# schema_v2_0.net
KiCad netlist of a schematic drawn in EAGLE
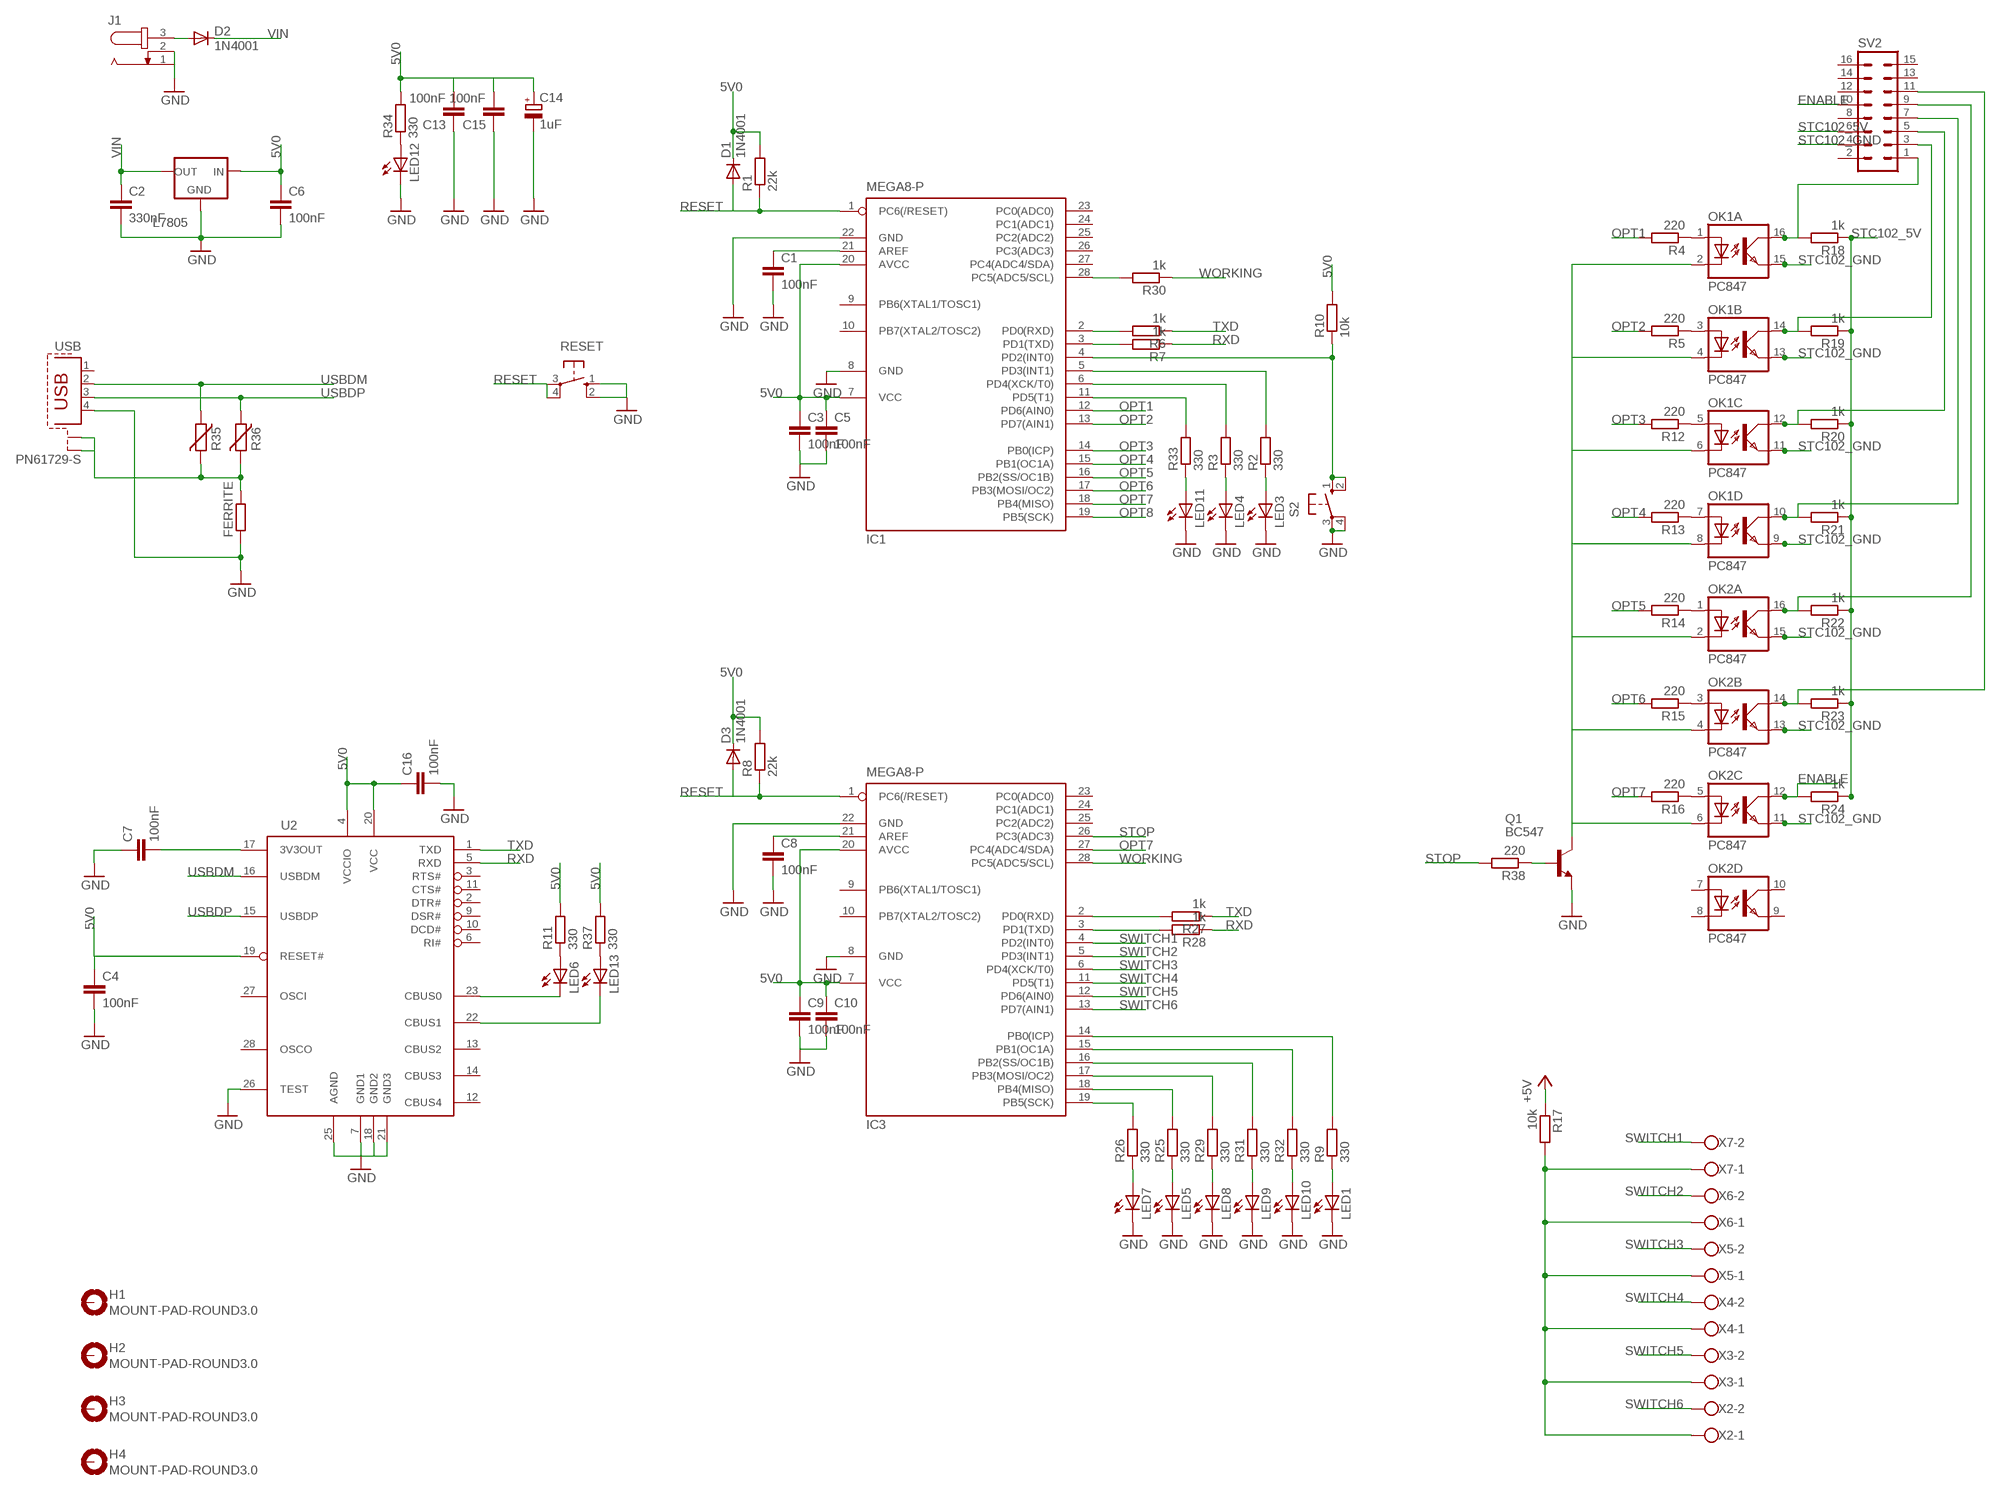
[diagram p0: schematic, sheet 1]

(export (version "E")
  (design (tool "Eeschema 10.0.6"))
  (components
    (comp (ref "C1")
      (value "100nF")
      (footprint "eagle-import:C025-025X050")
      (libsource (lib "eagle-import") (part "C-EU025-025X050"))
    )
    (comp (ref "C2")
      (value "330nF")
      (footprint "eagle-import:C025-025X050")
      (libsource (lib "eagle-import") (part "C-EU025-025X050"))
    )
    (comp (ref "C3")
      (value "100nF")
      (footprint "eagle-import:C025-025X050")
      (libsource (lib "eagle-import") (part "C-EU025-025X050"))
    )
    (comp (ref "C4")
      (value "100nF")
      (footprint "eagle-import:C0603K")
      (libsource (lib "eagle-import") (part "C-EUC0603K"))
    )
    (comp (ref "C5")
      (value "100nF")
      (footprint "eagle-import:C025-025X050")
      (libsource (lib "eagle-import") (part "C-EU025-025X050"))
    )
    (comp (ref "C6")
      (value "100nF")
      (footprint "eagle-import:C025-025X050")
      (libsource (lib "eagle-import") (part "C-EU025-025X050"))
    )
    (comp (ref "C7")
      (value "100nF")
      (footprint "eagle-import:C0603K")
      (libsource (lib "eagle-import") (part "C-EUC0603K"))
    )
    (comp (ref "C8")
      (value "100nF")
      (footprint "eagle-import:C025-025X050")
      (libsource (lib "eagle-import") (part "C-EU025-025X050"))
    )
    (comp (ref "C9")
      (value "100nF")
      (footprint "eagle-import:C025-025X050")
      (libsource (lib "eagle-import") (part "C-EU025-025X050"))
    )
    (comp (ref "C10")
      (value "100nF")
      (footprint "eagle-import:C025-025X050")
      (libsource (lib "eagle-import") (part "C-EU025-025X050"))
    )
    (comp (ref "C13")
      (value "100nF")
      (footprint "eagle-import:C025-025X050")
      (libsource (lib "eagle-import") (part "C-EU025-025X050"))
    )
    (comp (ref "C14")
      (value "1uF")
      (footprint "eagle-import:E2,5-5")
      (libsource (lib "eagle-import") (part "CPOL-EUE2.5-5"))
    )
    (comp (ref "C15")
      (value "100nF")
      (footprint "eagle-import:C025-025X050")
      (libsource (lib "eagle-import") (part "C-EU025-025X050"))
    )
    (comp (ref "C16")
      (value "100nF")
      (footprint "eagle-import:C0603K")
      (libsource (lib "eagle-import") (part "C-EUC0603K"))
    )
    (comp (ref "D1")
      (value "1N4001")
      (footprint "eagle-import:DO41-10")
      (libsource (lib "eagle-import") (part "1N4004"))
    )
    (comp (ref "D2")
      (value "1N4001")
      (footprint "eagle-import:DO41-10")
      (libsource (lib "eagle-import") (part "1N4004"))
    )
    (comp (ref "D3")
      (value "1N4001")
      (footprint "eagle-import:DO41-10")
      (libsource (lib "eagle-import") (part "1N4004"))
    )
    (comp (ref "FERRITE")
      (value "R-EU_M0805")
      (footprint "eagle-import:M0805")
      (libsource (lib "eagle-import") (part "resistor_R-EU_M0805"))
    )
    (comp (ref "H1")
      (value "MOUNT-PAD-ROUND3.0")
      (footprint "eagle-import:3,0-PAD")
      (libsource (lib "eagle-import") (part "MOUNT-PAD-ROUND3.0"))
    )
    (comp (ref "H2")
      (value "MOUNT-PAD-ROUND3.0")
      (footprint "eagle-import:3,0-PAD")
      (libsource (lib "eagle-import") (part "MOUNT-PAD-ROUND3.0"))
    )
    (comp (ref "H3")
      (value "MOUNT-PAD-ROUND3.0")
      (footprint "eagle-import:3,0-PAD")
      (libsource (lib "eagle-import") (part "MOUNT-PAD-ROUND3.0"))
    )
    (comp (ref "H4")
      (value "MOUNT-PAD-ROUND3.0")
      (footprint "eagle-import:3,0-PAD")
      (libsource (lib "eagle-import") (part "MOUNT-PAD-ROUND3.0"))
    )
    (comp (ref "IC1")
      (value "MEGA8-P")
      (footprint "eagle-import:DIL28-3")
      (libsource (lib "eagle-import") (part "MEGA8-P"))
    )
    (comp (ref "IC3")
      (value "MEGA8-P")
      (footprint "eagle-import:DIL28-3")
      (libsource (lib "eagle-import") (part "MEGA8-P"))
    )
    (comp (ref "J1")
      (value "JACK-PLUG0")
      (footprint "eagle-import:SPC4077")
      (libsource (lib "eagle-import") (part "JACK-PLUG0"))
    )
    (comp (ref "L7805")
      (value "79XXS")
      (footprint "eagle-import:79XXS")
      (libsource (lib "eagle-import") (part "79XXS"))
    )
    (comp (ref "LED1")
      (value "LED3MM")
      (footprint "eagle-import:LED3MM")
      (libsource (lib "eagle-import") (part "LED3MM"))
    )
    (comp (ref "LED3")
      (value "LED3MM")
      (footprint "eagle-import:LED3MM")
      (libsource (lib "eagle-import") (part "LED3MM"))
    )
    (comp (ref "LED4")
      (value "LED3MM")
      (footprint "eagle-import:LED3MM")
      (libsource (lib "eagle-import") (part "LED3MM"))
    )
    (comp (ref "LED5")
      (value "LED3MM")
      (footprint "eagle-import:LED3MM")
      (libsource (lib "eagle-import") (part "LED3MM"))
    )
    (comp (ref "LED6")
      (value "LED3MM")
      (footprint "eagle-import:LED3MM")
      (libsource (lib "eagle-import") (part "LED3MM"))
    )
    (comp (ref "LED7")
      (value "LED3MM")
      (footprint "eagle-import:LED3MM")
      (libsource (lib "eagle-import") (part "LED3MM"))
    )
    (comp (ref "LED8")
      (value "LED3MM")
      (footprint "eagle-import:LED3MM")
      (libsource (lib "eagle-import") (part "LED3MM"))
    )
    (comp (ref "LED9")
      (value "LED3MM")
      (footprint "eagle-import:LED3MM")
      (libsource (lib "eagle-import") (part "LED3MM"))
    )
    (comp (ref "LED10")
      (value "LED3MM")
      (footprint "eagle-import:LED3MM")
      (libsource (lib "eagle-import") (part "LED3MM"))
    )
    (comp (ref "LED11")
      (value "LED3MM")
      (footprint "eagle-import:LED3MM")
      (libsource (lib "eagle-import") (part "LED3MM"))
    )
    (comp (ref "LED12")
      (value "LED3MM")
      (footprint "eagle-import:LED3MM")
      (libsource (lib "eagle-import") (part "LED3MM"))
    )
    (comp (ref "LED13")
      (value "LED3MM")
      (footprint "eagle-import:LED3MM")
      (libsource (lib "eagle-import") (part "LED3MM"))
    )
    (comp (ref "OK1")
      (value "PC847")
      (footprint "eagle-import:DIL16")
      (libsource (lib "eagle-import") (part "PC847"))
    )
    (comp (ref "OK2")
      (value "PC847")
      (footprint "eagle-import:DIL16")
      (libsource (lib "eagle-import") (part "PC847"))
    )
    (comp (ref "Q1")
      (value "BC547")
      (footprint "eagle-import:TO92")
      (libsource (lib "eagle-import") (part "BC547"))
    )
    (comp (ref "R1")
      (value "22k")
      (footprint "eagle-import:0207_10")
      (libsource (lib "eagle-import") (part "R-EU_0207/10"))
    )
    (comp (ref "R2")
      (value "330")
      (footprint "eagle-import:0207_10")
      (libsource (lib "eagle-import") (part "R-EU_0207/10"))
    )
    (comp (ref "R3")
      (value "330")
      (footprint "eagle-import:0207_10")
      (libsource (lib "eagle-import") (part "R-EU_0207/10"))
    )
    (comp (ref "R4")
      (value "220")
      (footprint "eagle-import:0207_10")
      (libsource (lib "eagle-import") (part "R-EU_0207/10"))
    )
    (comp (ref "R5")
      (value "220")
      (footprint "eagle-import:0207_10")
      (libsource (lib "eagle-import") (part "R-EU_0207/10"))
    )
    (comp (ref "R6")
      (value "1k")
      (footprint "eagle-import:M1206")
      (libsource (lib "eagle-import") (part "R-EU_M1206"))
    )
    (comp (ref "R7")
      (value "1k")
      (footprint "eagle-import:M1206")
      (libsource (lib "eagle-import") (part "R-EU_M1206"))
    )
    (comp (ref "R8")
      (value "22k")
      (footprint "eagle-import:0207_10")
      (libsource (lib "eagle-import") (part "R-EU_0207/10"))
    )
    (comp (ref "R9")
      (value "330")
      (footprint "eagle-import:0207_10")
      (libsource (lib "eagle-import") (part "R-EU_0207/10"))
    )
    (comp (ref "R10")
      (value "10k")
      (footprint "eagle-import:0207_10")
      (libsource (lib "eagle-import") (part "R-EU_0207/10"))
    )
    (comp (ref "R11")
      (value "330")
      (footprint "eagle-import:0207_10")
      (libsource (lib "eagle-import") (part "R-EU_0207/10"))
    )
    (comp (ref "R12")
      (value "220")
      (footprint "eagle-import:0207_10")
      (libsource (lib "eagle-import") (part "R-EU_0207/10"))
    )
    (comp (ref "R13")
      (value "220")
      (footprint "eagle-import:0207_10")
      (libsource (lib "eagle-import") (part "R-EU_0207/10"))
    )
    (comp (ref "R14")
      (value "220")
      (footprint "eagle-import:0207_10")
      (libsource (lib "eagle-import") (part "R-EU_0207/10"))
    )
    (comp (ref "R15")
      (value "220")
      (footprint "eagle-import:0207_10")
      (libsource (lib "eagle-import") (part "R-EU_0207/10"))
    )
    (comp (ref "R16")
      (value "220")
      (footprint "eagle-import:0207_10")
      (libsource (lib "eagle-import") (part "R-EU_0207/10"))
    )
    (comp (ref "R17")
      (value "10k")
      (footprint "eagle-import:0207_10")
      (libsource (lib "eagle-import") (part "R-EU_0207/10"))
    )
    (comp (ref "R18")
      (value "1k")
      (footprint "eagle-import:0207_10")
      (libsource (lib "eagle-import") (part "R-EU_0207/10"))
    )
    (comp (ref "R19")
      (value "1k")
      (footprint "eagle-import:0207_10")
      (libsource (lib "eagle-import") (part "R-EU_0207/10"))
    )
    (comp (ref "R20")
      (value "1k")
      (footprint "eagle-import:0207_10")
      (libsource (lib "eagle-import") (part "R-EU_0207/10"))
    )
    (comp (ref "R21")
      (value "1k")
      (footprint "eagle-import:0207_10")
      (libsource (lib "eagle-import") (part "R-EU_0207/10"))
    )
    (comp (ref "R22")
      (value "1k")
      (footprint "eagle-import:0207_10")
      (libsource (lib "eagle-import") (part "R-EU_0207/10"))
    )
    (comp (ref "R23")
      (value "1k")
      (footprint "eagle-import:0207_10")
      (libsource (lib "eagle-import") (part "R-EU_0207/10"))
    )
    (comp (ref "R24")
      (value "1k")
      (footprint "eagle-import:0207_10")
      (libsource (lib "eagle-import") (part "R-EU_0207/10"))
    )
    (comp (ref "R25")
      (value "330")
      (footprint "eagle-import:0207_10")
      (libsource (lib "eagle-import") (part "R-EU_0207/10"))
    )
    (comp (ref "R26")
      (value "330")
      (footprint "eagle-import:0207_10")
      (libsource (lib "eagle-import") (part "R-EU_0207/10"))
    )
    (comp (ref "R27")
      (value "1k")
      (footprint "eagle-import:M1206")
      (libsource (lib "eagle-import") (part "R-EU_M1206"))
    )
    (comp (ref "R28")
      (value "1k")
      (footprint "eagle-import:M1206")
      (libsource (lib "eagle-import") (part "R-EU_M1206"))
    )
    (comp (ref "R29")
      (value "330")
      (footprint "eagle-import:0207_10")
      (libsource (lib "eagle-import") (part "R-EU_0207/10"))
    )
    (comp (ref "R30")
      (value "1k")
      (footprint "eagle-import:M1206")
      (libsource (lib "eagle-import") (part "R-EU_M1206"))
    )
    (comp (ref "R31")
      (value "330")
      (footprint "eagle-import:0207_10")
      (libsource (lib "eagle-import") (part "R-EU_0207/10"))
    )
    (comp (ref "R32")
      (value "330")
      (footprint "eagle-import:0207_10")
      (libsource (lib "eagle-import") (part "R-EU_0207/10"))
    )
    (comp (ref "R33")
      (value "330")
      (footprint "eagle-import:0207_10")
      (libsource (lib "eagle-import") (part "R-EU_0207/10"))
    )
    (comp (ref "R34")
      (value "330")
      (footprint "eagle-import:0207_10")
      (libsource (lib "eagle-import") (part "R-EU_0207/10"))
    )
    (comp (ref "R35")
      (value "VARISTORCN0603")
      (footprint "eagle-import:CT_CN0603")
      (libsource (lib "eagle-import") (part "VARISTORCN0603"))
    )
    (comp (ref "R36")
      (value "VARISTORCN0603")
      (footprint "eagle-import:CT_CN0603")
      (libsource (lib "eagle-import") (part "VARISTORCN0603"))
    )
    (comp (ref "R37")
      (value "330")
      (footprint "eagle-import:0207_10")
      (libsource (lib "eagle-import") (part "R-EU_0207/10"))
    )
    (comp (ref "R38")
      (value "220")
      (footprint "eagle-import:0207_10")
      (libsource (lib "eagle-import") (part "R-EU_0207/10"))
    )
    (comp (ref "RESET")
      (value "10-XX")
      (footprint "eagle-import:B3F-10XX")
      (fields (field (name "MPN") "B3F-1000"))
      (libsource (lib "eagle-import") (part "10-XX"))
    )
    (comp (ref "S2")
      (value "10-XX")
      (footprint "eagle-import:B3F-10XX")
      (fields (field (name "MPN") "B3F-1000"))
      (libsource (lib "eagle-import") (part "10-XX"))
    )
    (comp (ref "SV2")
      (value "MA08-2")
      (footprint "eagle-import:MA08-2")
      (libsource (lib "eagle-import") (part "MA08-2"))
    )
    (comp (ref "U2")
      (value "FT232RL")
      (footprint "eagle-import:SSOP28DB")
      (libsource (lib "eagle-import") (part "FT232RL"))
    )
    (comp (ref "USB")
      (value "PN61729-S")
      (footprint "eagle-import:PN61729-S")
      (fields (field (name "OC_FARNELL") "unknown") (field (name "OC_NEWARK") "unknown"))
      (libsource (lib "eagle-import") (part "PN61729-S"))
    )
    (comp (ref "X2")
      (value "W237-102")
      (footprint "eagle-import:W237-102")
      (fields (field (name "MPN") "237-102"))
      (libsource (lib "eagle-import") (part "W237-102"))
    )
    (comp (ref "X3")
      (value "W237-102")
      (footprint "eagle-import:W237-102")
      (fields (field (name "MPN") "237-102"))
      (libsource (lib "eagle-import") (part "W237-102"))
    )
    (comp (ref "X4")
      (value "W237-102")
      (footprint "eagle-import:W237-102")
      (fields (field (name "MPN") "237-102"))
      (libsource (lib "eagle-import") (part "W237-102"))
    )
    (comp (ref "X5")
      (value "W237-102")
      (footprint "eagle-import:W237-102")
      (fields (field (name "MPN") "237-102"))
      (libsource (lib "eagle-import") (part "W237-102"))
    )
    (comp (ref "X6")
      (value "W237-102")
      (footprint "eagle-import:W237-102")
      (fields (field (name "MPN") "237-102"))
      (libsource (lib "eagle-import") (part "W237-102"))
    )
    (comp (ref "X7")
      (value "W237-102")
      (footprint "eagle-import:W237-102")
      (fields (field (name "MPN") "237-102"))
      (libsource (lib "eagle-import") (part "W237-102"))
    )
  )
  (nets
    (net (code "1") (name "+5V") (class "Default")
      (node (ref "R17") (pin "1") (pinfunction "1_1") (pintype "passive"))
    )
    (net (code "2") (name "/5V0") (class "Default")
      (node (ref "C10") (pin "1") (pinfunction "1_1") (pintype "passive"))
      (node (ref "C13") (pin "2") (pinfunction "2_2") (pintype "passive"))
      (node (ref "C14") (pin "+") (pinfunction "+_+") (pintype "passive"))
      (node (ref "C15") (pin "2") (pinfunction "2_2") (pintype "passive"))
      (node (ref "C16") (pin "1") (pinfunction "1_1") (pintype "passive"))
      (node (ref "C3") (pin "1") (pinfunction "1_1") (pintype "passive"))
      (node (ref "C4") (pin "1") (pinfunction "1_1") (pintype "passive"))
      (node (ref "C5") (pin "1") (pinfunction "1_1") (pintype "passive"))
      (node (ref "C6") (pin "1") (pinfunction "1_1") (pintype "passive"))
      (node (ref "C9") (pin "1") (pinfunction "1_1") (pintype "passive"))
      (node (ref "D1") (pin "C") (pinfunction "C_C") (pintype "passive"))
      (node (ref "D3") (pin "C") (pinfunction "C_C") (pintype "passive"))
      (node (ref "IC1") (pin "20") (pinfunction "AVCC_20") (pintype "power_in"))
      (node (ref "IC1") (pin "7") (pinfunction "VCC_7") (pintype "power_in"))
      (node (ref "IC3") (pin "20") (pinfunction "AVCC_20") (pintype "power_in"))
      (node (ref "IC3") (pin "7") (pinfunction "VCC_7") (pintype "power_in"))
      (node (ref "L7805") (pin "IN") (pinfunction "IN_IN") (pintype "input"))
      (node (ref "R1") (pin "2") (pinfunction "2_2") (pintype "passive"))
      (node (ref "R10") (pin "2") (pinfunction "2_2") (pintype "passive"))
      (node (ref "R11") (pin "2") (pinfunction "2_2") (pintype "passive"))
      (node (ref "R34") (pin "2") (pinfunction "2_2") (pintype "passive"))
      (node (ref "R37") (pin "2") (pinfunction "2_2") (pintype "passive"))
      (node (ref "R8") (pin "2") (pinfunction "2_2") (pintype "passive"))
      (node (ref "U2") (pin "19") (pinfunction "RESET#_19") (pintype "input"))
      (node (ref "U2") (pin "20") (pinfunction "VCC_20") (pintype "power_in"))
      (node (ref "U2") (pin "4") (pinfunction "VCCIO_4") (pintype "power_in"))
    )
    (net (code "3") (name "/ENABLE") (class "Default")
      (node (ref "OK2") (pin "12") (pinfunction "COL_12") (pintype "passive"))
      (node (ref "R24") (pin "2") (pinfunction "2_2") (pintype "passive"))
      (node (ref "SV2") (pin "10") (pinfunction "10_10") (pintype "passive"))
    )
    (net (code "4") (name "/OPT1") (class "Default")
      (node (ref "IC1") (pin "12") (pinfunction "PD6(AIN0)_12") (pintype "bidirectional"))
      (node (ref "R4") (pin "2") (pinfunction "2_2") (pintype "passive"))
    )
    (net (code "5") (name "/OPT2") (class "Default")
      (node (ref "IC1") (pin "13") (pinfunction "PD7(AIN1)_13") (pintype "bidirectional"))
      (node (ref "R5") (pin "2") (pinfunction "2_2") (pintype "passive"))
    )
    (net (code "6") (name "/OPT3") (class "Default")
      (node (ref "IC1") (pin "14") (pinfunction "PB0(ICP)_14") (pintype "bidirectional"))
      (node (ref "R12") (pin "2") (pinfunction "2_2") (pintype "passive"))
    )
    (net (code "7") (name "/OPT4") (class "Default")
      (node (ref "IC1") (pin "15") (pinfunction "PB1(OC1A)_15") (pintype "bidirectional"))
      (node (ref "R13") (pin "2") (pinfunction "2_2") (pintype "passive"))
    )
    (net (code "8") (name "/OPT5") (class "Default")
      (node (ref "IC1") (pin "16") (pinfunction "PB2(SS/OC1B)_16") (pintype "bidirectional"))
      (node (ref "R14") (pin "2") (pinfunction "2_2") (pintype "passive"))
    )
    (net (code "9") (name "/OPT6") (class "Default")
      (node (ref "IC1") (pin "17") (pinfunction "PB3(MOSI/OC2)_17") (pintype "bidirectional"))
      (node (ref "R15") (pin "2") (pinfunction "2_2") (pintype "passive"))
    )
    (net (code "10") (name "/OPT7") (class "Default")
      (node (ref "IC1") (pin "18") (pinfunction "PB4(MISO)_18") (pintype "bidirectional"))
      (node (ref "IC3") (pin "27") (pinfunction "PC4(ADC4/SDA)_27") (pintype "bidirectional"))
      (node (ref "R16") (pin "2") (pinfunction "2_2") (pintype "passive"))
    )
    (net (code "11") (name "/OPT8") (class "Default")
      (node (ref "IC1") (pin "19") (pinfunction "PB5(SCK)_19") (pintype "bidirectional"))
    )
    (net (code "12") (name "/RESET") (class "Default")
      (node (ref "D1") (pin "A") (pinfunction "A_A") (pintype "passive"))
      (node (ref "D3") (pin "A") (pinfunction "A_A") (pintype "passive"))
      (node (ref "IC1") (pin "1") (pinfunction "PC6(/RESET)_1") (pintype "bidirectional"))
      (node (ref "IC3") (pin "1") (pinfunction "PC6(/RESET)_1") (pintype "bidirectional"))
      (node (ref "R1") (pin "1") (pinfunction "1_1") (pintype "passive"))
      (node (ref "R8") (pin "1") (pinfunction "1_1") (pintype "passive"))
      (node (ref "RESET") (pin "3") (pinfunction "P_3") (pintype "passive"))
      (node (ref "RESET") (pin "4") (pinfunction "P1_4") (pintype "passive"))
    )
    (net (code "13") (name "/RXD") (class "Default")
      (node (ref "R28") (pin "1") (pinfunction "1_1") (pintype "passive"))
      (node (ref "R7") (pin "1") (pinfunction "1_1") (pintype "passive"))
      (node (ref "U2") (pin "5") (pinfunction "RXD_5") (pintype "input"))
    )
    (net (code "14") (name "/STC102_5V") (class "Default")
      (node (ref "R18") (pin "1") (pinfunction "1_1") (pintype "passive"))
      (node (ref "R19") (pin "1") (pinfunction "1_1") (pintype "passive"))
      (node (ref "R20") (pin "1") (pinfunction "1_1") (pintype "passive"))
      (node (ref "R21") (pin "1") (pinfunction "1_1") (pintype "passive"))
      (node (ref "R22") (pin "1") (pinfunction "1_1") (pintype "passive"))
      (node (ref "R23") (pin "1") (pinfunction "1_1") (pintype "passive"))
      (node (ref "R24") (pin "1") (pinfunction "1_1") (pintype "passive"))
      (node (ref "SV2") (pin "6") (pinfunction "6_6") (pintype "passive"))
    )
    (net (code "15") (name "/STC102_GND") (class "Default")
      (node (ref "OK1") (pin "11") (pinfunction "EMIT_11") (pintype "passive"))
      (node (ref "OK1") (pin "13") (pinfunction "EMIT_13") (pintype "passive"))
      (node (ref "OK1") (pin "15") (pinfunction "EMIT_15") (pintype "passive"))
      (node (ref "OK1") (pin "9") (pinfunction "EMIT_9") (pintype "passive"))
      (node (ref "OK2") (pin "11") (pinfunction "EMIT_11") (pintype "passive"))
      (node (ref "OK2") (pin "13") (pinfunction "EMIT_13") (pintype "passive"))
      (node (ref "OK2") (pin "15") (pinfunction "EMIT_15") (pintype "passive"))
      (node (ref "SV2") (pin "4") (pinfunction "4_4") (pintype "passive"))
    )
    (net (code "16") (name "/STOP") (class "Default")
      (node (ref "IC3") (pin "26") (pinfunction "PC3(ADC3)_26") (pintype "bidirectional"))
      (node (ref "R38") (pin "2") (pinfunction "2_2") (pintype "passive"))
    )
    (net (code "17") (name "/SWITCH1") (class "Default")
      (node (ref "IC3") (pin "4") (pinfunction "PD2(INT0)_4") (pintype "bidirectional"))
      (node (ref "X7") (pin "2") (pinfunction "KL_2") (pintype "passive"))
    )
    (net (code "18") (name "/SWITCH2") (class "Default")
      (node (ref "IC3") (pin "5") (pinfunction "PD3(INT1)_5") (pintype "bidirectional"))
      (node (ref "X6") (pin "2") (pinfunction "KL_2") (pintype "passive"))
    )
    (net (code "19") (name "/SWITCH3") (class "Default")
      (node (ref "IC3") (pin "6") (pinfunction "PD4(XCK/T0)_6") (pintype "bidirectional"))
      (node (ref "X5") (pin "2") (pinfunction "KL_2") (pintype "passive"))
    )
    (net (code "20") (name "/SWITCH4") (class "Default")
      (node (ref "IC3") (pin "11") (pinfunction "PD5(T1)_11") (pintype "bidirectional"))
      (node (ref "X4") (pin "2") (pinfunction "KL_2") (pintype "passive"))
    )
    (net (code "21") (name "/SWITCH5") (class "Default")
      (node (ref "IC3") (pin "12") (pinfunction "PD6(AIN0)_12") (pintype "bidirectional"))
      (node (ref "X3") (pin "2") (pinfunction "KL_2") (pintype "passive"))
    )
    (net (code "22") (name "/SWITCH6") (class "Default")
      (node (ref "IC3") (pin "13") (pinfunction "PD7(AIN1)_13") (pintype "bidirectional"))
      (node (ref "X2") (pin "2") (pinfunction "KL_2") (pintype "passive"))
    )
    (net (code "23") (name "/TXD") (class "Default")
      (node (ref "R27") (pin "1") (pinfunction "1_1") (pintype "passive"))
      (node (ref "R6") (pin "1") (pinfunction "1_1") (pintype "passive"))
      (node (ref "U2") (pin "1") (pinfunction "TXD_1") (pintype "output"))
    )
    (net (code "24") (name "/USBDM") (class "Default")
      (node (ref "R35") (pin "1") (pinfunction "1_1") (pintype "passive"))
      (node (ref "U2") (pin "16") (pinfunction "USBDM_16") (pintype "bidirectional"))
      (node (ref "USB") (pin "2") (pinfunction "2_2") (pintype "passive"))
    )
    (net (code "25") (name "/USBDP") (class "Default")
      (node (ref "R36") (pin "1") (pinfunction "1_1") (pintype "passive"))
      (node (ref "U2") (pin "15") (pinfunction "USBDP_15") (pintype "bidirectional"))
      (node (ref "USB") (pin "3") (pinfunction "3_3") (pintype "passive"))
    )
    (net (code "26") (name "/VIN") (class "Default")
      (node (ref "C2") (pin "1") (pinfunction "1_1") (pintype "passive"))
      (node (ref "D2") (pin "C") (pinfunction "C_C") (pintype "passive"))
      (node (ref "L7805") (pin "OUT") (pinfunction "OUT_OUT") (pintype "passive"))
    )
    (net (code "27") (name "/WORKING") (class "Default")
      (node (ref "IC3") (pin "28") (pinfunction "PC5(ADC5/SCL)_28") (pintype "bidirectional"))
      (node (ref "R30") (pin "1") (pinfunction "1_1") (pintype "passive"))
    )
    (net (code "28") (name "GND") (class "Default")
      (node (ref "C1") (pin "2") (pinfunction "2_2") (pintype "passive"))
      (node (ref "C10") (pin "2") (pinfunction "2_2") (pintype "passive"))
      (node (ref "C13") (pin "1") (pinfunction "1_1") (pintype "passive"))
      (node (ref "C14") (pin "-") (pinfunction "-_-") (pintype "passive"))
      (node (ref "C15") (pin "1") (pinfunction "1_1") (pintype "passive"))
      (node (ref "C16") (pin "2") (pinfunction "2_2") (pintype "passive"))
      (node (ref "C2") (pin "2") (pinfunction "2_2") (pintype "passive"))
      (node (ref "C3") (pin "2") (pinfunction "2_2") (pintype "passive"))
      (node (ref "C4") (pin "2") (pinfunction "2_2") (pintype "passive"))
      (node (ref "C5") (pin "2") (pinfunction "2_2") (pintype "passive"))
      (node (ref "C6") (pin "2") (pinfunction "2_2") (pintype "passive"))
      (node (ref "C7") (pin "1") (pinfunction "1_1") (pintype "passive"))
      (node (ref "C8") (pin "2") (pinfunction "2_2") (pintype "passive"))
      (node (ref "C9") (pin "2") (pinfunction "2_2") (pintype "passive"))
      (node (ref "FERRITE") (pin "1") (pinfunction "1_1") (pintype "passive"))
      (node (ref "IC1") (pin "22") (pinfunction "GND_22") (pintype "power_in"))
      (node (ref "IC1") (pin "8") (pinfunction "GND_8") (pintype "power_in"))
      (node (ref "IC3") (pin "22") (pinfunction "GND_22") (pintype "power_in"))
      (node (ref "IC3") (pin "8") (pinfunction "GND_8") (pintype "power_in"))
      (node (ref "J1") (pin "1") (pinfunction "1_1") (pintype "passive"))
      (node (ref "J1") (pin "2") (pinfunction "2_2") (pintype "passive"))
      (node (ref "L7805") (pin "GND") (pinfunction "GND_GND") (pintype "input"))
      (node (ref "LED1") (pin "K") (pinfunction "C_K") (pintype "passive"))
      (node (ref "LED10") (pin "K") (pinfunction "C_K") (pintype "passive"))
      (node (ref "LED11") (pin "K") (pinfunction "C_K") (pintype "passive"))
      (node (ref "LED12") (pin "K") (pinfunction "C_K") (pintype "passive"))
      (node (ref "LED3") (pin "K") (pinfunction "C_K") (pintype "passive"))
      (node (ref "LED4") (pin "K") (pinfunction "C_K") (pintype "passive"))
      (node (ref "LED5") (pin "K") (pinfunction "C_K") (pintype "passive"))
      (node (ref "LED7") (pin "K") (pinfunction "C_K") (pintype "passive"))
      (node (ref "LED8") (pin "K") (pinfunction "C_K") (pintype "passive"))
      (node (ref "LED9") (pin "K") (pinfunction "C_K") (pintype "passive"))
      (node (ref "Q1") (pin "1") (pinfunction "E_1") (pintype "passive"))
      (node (ref "RESET") (pin "1") (pinfunction "S_1") (pintype "passive"))
      (node (ref "RESET") (pin "2") (pinfunction "S1_2") (pintype "passive"))
      (node (ref "S2") (pin "3") (pinfunction "P_3") (pintype "passive"))
      (node (ref "S2") (pin "4") (pinfunction "P1_4") (pintype "passive"))
      (node (ref "U2") (pin "18") (pinfunction "GND2_18") (pintype "power_in"))
      (node (ref "U2") (pin "21") (pinfunction "GND3_21") (pintype "power_in"))
      (node (ref "U2") (pin "25") (pinfunction "AGND_25") (pintype "power_in"))
      (node (ref "U2") (pin "26") (pinfunction "TEST_26") (pintype "input"))
      (node (ref "U2") (pin "7") (pinfunction "GND1_7") (pintype "power_in"))
      (node (ref "USB") (pin "4") (pinfunction "4_4") (pintype "passive"))
    )
    (net (code "29") (name "Net-(D2-PadA)") (class "Default")
      (node (ref "D2") (pin "A") (pinfunction "A_A") (pintype "passive"))
      (node (ref "J1") (pin "3") (pinfunction "3_3") (pintype "passive"))
    )
    (net (code "30") (name "Net-(FERRITE-Pad2)") (class "Default")
      (node (ref "FERRITE") (pin "2") (pinfunction "2_2") (pintype "passive"))
      (node (ref "R35") (pin "2") (pinfunction "2_2") (pintype "passive"))
      (node (ref "R36") (pin "2") (pinfunction "2_2") (pintype "passive"))
      (node (ref "USB") (pin "S1") (pinfunction "S1_S1") (pintype "passive"))
      (node (ref "USB") (pin "S2") (pinfunction "S2_S2") (pintype "passive"))
    )
    (net (code "31") (name "Net-(IC1-AREF)") (class "Default")
      (node (ref "C1") (pin "1") (pinfunction "1_1") (pintype "passive"))
      (node (ref "IC1") (pin "21") (pinfunction "AREF_21") (pintype "passive"))
    )
    (net (code "32") (name "Net-(IC1-PC5(ADC5{slash}SCL))") (class "Default")
      (node (ref "IC1") (pin "28") (pinfunction "PC5(ADC5/SCL)_28") (pintype "bidirectional"))
      (node (ref "R30") (pin "2") (pinfunction "2_2") (pintype "passive"))
    )
    (net (code "33") (name "Net-(IC1-PD0(RXD))") (class "Default")
      (node (ref "IC1") (pin "2") (pinfunction "PD0(RXD)_2") (pintype "bidirectional"))
      (node (ref "R6") (pin "2") (pinfunction "2_2") (pintype "passive"))
    )
    (net (code "34") (name "Net-(IC1-PD1(TXD))") (class "Default")
      (node (ref "IC1") (pin "3") (pinfunction "PD1(TXD)_3") (pintype "bidirectional"))
      (node (ref "R7") (pin "2") (pinfunction "2_2") (pintype "passive"))
    )
    (net (code "35") (name "Net-(IC1-PD2(INT0))") (class "Default")
      (node (ref "IC1") (pin "4") (pinfunction "PD2(INT0)_4") (pintype "bidirectional"))
      (node (ref "R10") (pin "1") (pinfunction "1_1") (pintype "passive"))
      (node (ref "S2") (pin "1") (pinfunction "S_1") (pintype "passive"))
      (node (ref "S2") (pin "2") (pinfunction "S1_2") (pintype "passive"))
    )
    (net (code "36") (name "Net-(IC1-PD3(INT1))") (class "Default")
      (node (ref "IC1") (pin "5") (pinfunction "PD3(INT1)_5") (pintype "bidirectional"))
      (node (ref "R2") (pin "2") (pinfunction "2_2") (pintype "passive"))
    )
    (net (code "37") (name "Net-(IC1-PD4(XCK{slash}T0))") (class "Default")
      (node (ref "IC1") (pin "6") (pinfunction "PD4(XCK/T0)_6") (pintype "bidirectional"))
      (node (ref "R3") (pin "2") (pinfunction "2_2") (pintype "passive"))
    )
    (net (code "38") (name "Net-(IC1-PD5(T1))") (class "Default")
      (node (ref "IC1") (pin "11") (pinfunction "PD5(T1)_11") (pintype "bidirectional"))
      (node (ref "R33") (pin "2") (pinfunction "2_2") (pintype "passive"))
    )
    (net (code "39") (name "Net-(IC3-AREF)") (class "Default")
      (node (ref "C8") (pin "1") (pinfunction "1_1") (pintype "passive"))
      (node (ref "IC3") (pin "21") (pinfunction "AREF_21") (pintype "passive"))
    )
    (net (code "40") (name "Net-(IC3-PB0(ICP))") (class "Default")
      (node (ref "IC3") (pin "14") (pinfunction "PB0(ICP)_14") (pintype "bidirectional"))
      (node (ref "R9") (pin "2") (pinfunction "2_2") (pintype "passive"))
    )
    (net (code "41") (name "Net-(IC3-PB1(OC1A))") (class "Default")
      (node (ref "IC3") (pin "15") (pinfunction "PB1(OC1A)_15") (pintype "bidirectional"))
      (node (ref "R32") (pin "2") (pinfunction "2_2") (pintype "passive"))
    )
    (net (code "42") (name "Net-(IC3-PB2(SS{slash}OC1B))") (class "Default")
      (node (ref "IC3") (pin "16") (pinfunction "PB2(SS/OC1B)_16") (pintype "bidirectional"))
      (node (ref "R31") (pin "2") (pinfunction "2_2") (pintype "passive"))
    )
    (net (code "43") (name "Net-(IC3-PB3(MOSI{slash}OC2))") (class "Default")
      (node (ref "IC3") (pin "17") (pinfunction "PB3(MOSI/OC2)_17") (pintype "bidirectional"))
      (node (ref "R29") (pin "2") (pinfunction "2_2") (pintype "passive"))
    )
    (net (code "44") (name "Net-(IC3-PB4(MISO))") (class "Default")
      (node (ref "IC3") (pin "18") (pinfunction "PB4(MISO)_18") (pintype "bidirectional"))
      (node (ref "R25") (pin "2") (pinfunction "2_2") (pintype "passive"))
    )
    (net (code "45") (name "Net-(IC3-PB5(SCK))") (class "Default")
      (node (ref "IC3") (pin "19") (pinfunction "PB5(SCK)_19") (pintype "bidirectional"))
      (node (ref "R26") (pin "2") (pinfunction "2_2") (pintype "passive"))
    )
    (net (code "46") (name "Net-(IC3-PD0(RXD))") (class "Default")
      (node (ref "IC3") (pin "2") (pinfunction "PD0(RXD)_2") (pintype "bidirectional"))
      (node (ref "R27") (pin "2") (pinfunction "2_2") (pintype "passive"))
    )
    (net (code "47") (name "Net-(IC3-PD1(TXD))") (class "Default")
      (node (ref "IC3") (pin "3") (pinfunction "PD1(TXD)_3") (pintype "bidirectional"))
      (node (ref "R28") (pin "2") (pinfunction "2_2") (pintype "passive"))
    )
    (net (code "48") (name "Net-(LED1-PadA)") (class "Default")
      (node (ref "LED1") (pin "A") (pinfunction "A_A") (pintype "passive"))
      (node (ref "R9") (pin "1") (pinfunction "1_1") (pintype "passive"))
    )
    (net (code "49") (name "Net-(LED3-PadA)") (class "Default")
      (node (ref "LED3") (pin "A") (pinfunction "A_A") (pintype "passive"))
      (node (ref "R2") (pin "1") (pinfunction "1_1") (pintype "passive"))
    )
    (net (code "50") (name "Net-(LED4-PadA)") (class "Default")
      (node (ref "LED4") (pin "A") (pinfunction "A_A") (pintype "passive"))
      (node (ref "R3") (pin "1") (pinfunction "1_1") (pintype "passive"))
    )
    (net (code "51") (name "Net-(LED5-PadA)") (class "Default")
      (node (ref "LED5") (pin "A") (pinfunction "A_A") (pintype "passive"))
      (node (ref "R25") (pin "1") (pinfunction "1_1") (pintype "passive"))
    )
    (net (code "52") (name "Net-(LED6-C)") (class "Default")
      (node (ref "LED6") (pin "K") (pinfunction "C_K") (pintype "passive"))
      (node (ref "U2") (pin "23") (pinfunction "CBUS0_23") (pintype "bidirectional"))
    )
    (net (code "53") (name "Net-(LED6-PadA)") (class "Default")
      (node (ref "LED6") (pin "A") (pinfunction "A_A") (pintype "passive"))
      (node (ref "R11") (pin "1") (pinfunction "1_1") (pintype "passive"))
    )
    (net (code "54") (name "Net-(LED7-PadA)") (class "Default")
      (node (ref "LED7") (pin "A") (pinfunction "A_A") (pintype "passive"))
      (node (ref "R26") (pin "1") (pinfunction "1_1") (pintype "passive"))
    )
    (net (code "55") (name "Net-(LED8-PadA)") (class "Default")
      (node (ref "LED8") (pin "A") (pinfunction "A_A") (pintype "passive"))
      (node (ref "R29") (pin "1") (pinfunction "1_1") (pintype "passive"))
    )
    (net (code "56") (name "Net-(LED9-PadA)") (class "Default")
      (node (ref "LED9") (pin "A") (pinfunction "A_A") (pintype "passive"))
      (node (ref "R31") (pin "1") (pinfunction "1_1") (pintype "passive"))
    )
    (net (code "57") (name "Net-(LED10-PadA)") (class "Default")
      (node (ref "LED10") (pin "A") (pinfunction "A_A") (pintype "passive"))
      (node (ref "R32") (pin "1") (pinfunction "1_1") (pintype "passive"))
    )
    (net (code "58") (name "Net-(LED11-PadA)") (class "Default")
      (node (ref "LED11") (pin "A") (pinfunction "A_A") (pintype "passive"))
      (node (ref "R33") (pin "1") (pinfunction "1_1") (pintype "passive"))
    )
    (net (code "59") (name "Net-(LED12-PadA)") (class "Default")
      (node (ref "LED12") (pin "A") (pinfunction "A_A") (pintype "passive"))
      (node (ref "R34") (pin "1") (pinfunction "1_1") (pintype "passive"))
    )
    (net (code "60") (name "Net-(LED13-C)") (class "Default")
      (node (ref "LED13") (pin "K") (pinfunction "C_K") (pintype "passive"))
      (node (ref "U2") (pin "22") (pinfunction "CBUS1_22") (pintype "bidirectional"))
    )
    (net (code "61") (name "Net-(LED13-PadA)") (class "Default")
      (node (ref "LED13") (pin "A") (pinfunction "A_A") (pintype "passive"))
      (node (ref "R37") (pin "1") (pinfunction "1_1") (pintype "passive"))
    )
    (net (code "62") (name "Net-(OK1A-A)") (class "Default")
      (node (ref "OK1") (pin "1") (pinfunction "A_1") (pintype "passive"))
      (node (ref "R4") (pin "1") (pinfunction "1_1") (pintype "passive"))
    )
    (net (code "63") (name "Net-(OK1A-C)") (class "Default")
      (node (ref "OK1") (pin "2") (pinfunction "C_2") (pintype "passive"))
      (node (ref "OK1") (pin "4") (pinfunction "C_4") (pintype "passive"))
      (node (ref "OK1") (pin "6") (pinfunction "C_6") (pintype "passive"))
      (node (ref "OK1") (pin "8") (pinfunction "C_8") (pintype "passive"))
      (node (ref "OK2") (pin "2") (pinfunction "C_2") (pintype "passive"))
      (node (ref "OK2") (pin "4") (pinfunction "C_4") (pintype "passive"))
      (node (ref "OK2") (pin "6") (pinfunction "C_6") (pintype "passive"))
      (node (ref "Q1") (pin "3") (pinfunction "C_3") (pintype "passive"))
    )
    (net (code "64") (name "Net-(OK1A-COL)") (class "Default")
      (node (ref "OK1") (pin "16") (pinfunction "COL_16") (pintype "passive"))
      (node (ref "R18") (pin "2") (pinfunction "2_2") (pintype "passive"))
      (node (ref "SV2") (pin "1") (pinfunction "1_1") (pintype "passive"))
    )
    (net (code "65") (name "Net-(OK1B-A)") (class "Default")
      (node (ref "OK1") (pin "3") (pinfunction "A_3") (pintype "passive"))
      (node (ref "R5") (pin "1") (pinfunction "1_1") (pintype "passive"))
    )
    (net (code "66") (name "Net-(OK1B-COL)") (class "Default")
      (node (ref "OK1") (pin "14") (pinfunction "COL_14") (pintype "passive"))
      (node (ref "R19") (pin "2") (pinfunction "2_2") (pintype "passive"))
      (node (ref "SV2") (pin "3") (pinfunction "3_3") (pintype "passive"))
    )
    (net (code "67") (name "Net-(OK1C-A)") (class "Default")
      (node (ref "OK1") (pin "5") (pinfunction "A_5") (pintype "passive"))
      (node (ref "R12") (pin "1") (pinfunction "1_1") (pintype "passive"))
    )
    (net (code "68") (name "Net-(OK1C-COL)") (class "Default")
      (node (ref "OK1") (pin "12") (pinfunction "COL_12") (pintype "passive"))
      (node (ref "R20") (pin "2") (pinfunction "2_2") (pintype "passive"))
      (node (ref "SV2") (pin "5") (pinfunction "5_5") (pintype "passive"))
    )
    (net (code "69") (name "Net-(OK1D-A)") (class "Default")
      (node (ref "OK1") (pin "7") (pinfunction "A_7") (pintype "passive"))
      (node (ref "R13") (pin "1") (pinfunction "1_1") (pintype "passive"))
    )
    (net (code "70") (name "Net-(OK1D-COL)") (class "Default")
      (node (ref "OK1") (pin "10") (pinfunction "COL_10") (pintype "passive"))
      (node (ref "R21") (pin "2") (pinfunction "2_2") (pintype "passive"))
      (node (ref "SV2") (pin "7") (pinfunction "7_7") (pintype "passive"))
    )
    (net (code "71") (name "Net-(OK2A-A)") (class "Default")
      (node (ref "OK2") (pin "1") (pinfunction "A_1") (pintype "passive"))
      (node (ref "R14") (pin "1") (pinfunction "1_1") (pintype "passive"))
    )
    (net (code "72") (name "Net-(OK2A-COL)") (class "Default")
      (node (ref "OK2") (pin "16") (pinfunction "COL_16") (pintype "passive"))
      (node (ref "R22") (pin "2") (pinfunction "2_2") (pintype "passive"))
      (node (ref "SV2") (pin "9") (pinfunction "9_9") (pintype "passive"))
    )
    (net (code "73") (name "Net-(OK2B-A)") (class "Default")
      (node (ref "OK2") (pin "3") (pinfunction "A_3") (pintype "passive"))
      (node (ref "R15") (pin "1") (pinfunction "1_1") (pintype "passive"))
    )
    (net (code "74") (name "Net-(OK2B-COL)") (class "Default")
      (node (ref "OK2") (pin "14") (pinfunction "COL_14") (pintype "passive"))
      (node (ref "R23") (pin "2") (pinfunction "2_2") (pintype "passive"))
      (node (ref "SV2") (pin "11") (pinfunction "11_11") (pintype "passive"))
    )
    (net (code "75") (name "Net-(OK2C-A)") (class "Default")
      (node (ref "OK2") (pin "5") (pinfunction "A_5") (pintype "passive"))
      (node (ref "R16") (pin "1") (pinfunction "1_1") (pintype "passive"))
    )
    (net (code "76") (name "Net-(Q1-B)") (class "Default")
      (node (ref "Q1") (pin "2") (pinfunction "B_2") (pintype "passive"))
      (node (ref "R38") (pin "1") (pinfunction "1_1") (pintype "passive"))
    )
    (net (code "77") (name "Net-(U2-3V3OUT)") (class "Default")
      (node (ref "C7") (pin "2") (pinfunction "2_2") (pintype "passive"))
      (node (ref "U2") (pin "17") (pinfunction "3V3OUT_17") (pintype "output"))
    )
    (net (code "78") (name "Net-(X2A-KL)") (class "Default")
      (node (ref "R17") (pin "2") (pinfunction "2_2") (pintype "passive"))
      (node (ref "X2") (pin "1") (pinfunction "KL_1") (pintype "passive"))
      (node (ref "X3") (pin "1") (pinfunction "KL_1") (pintype "passive"))
      (node (ref "X4") (pin "1") (pinfunction "KL_1") (pintype "passive"))
      (node (ref "X5") (pin "1") (pinfunction "KL_1") (pintype "passive"))
      (node (ref "X6") (pin "1") (pinfunction "KL_1") (pintype "passive"))
      (node (ref "X7") (pin "1") (pinfunction "KL_1") (pintype "passive"))
    )
    (net (code "79") (name "unconnected-(H1-MOUNT-PadB3,0)") (class "Default")
      (node (ref "H1") (pin "B3,0") (pinfunction "MOUNT_B3,0") (pintype "passive"))
    )
    (net (code "80") (name "unconnected-(H2-MOUNT-PadB3,0)") (class "Default")
      (node (ref "H2") (pin "B3,0") (pinfunction "MOUNT_B3,0") (pintype "passive"))
    )
    (net (code "81") (name "unconnected-(H3-MOUNT-PadB3,0)") (class "Default")
      (node (ref "H3") (pin "B3,0") (pinfunction "MOUNT_B3,0") (pintype "passive"))
    )
    (net (code "82") (name "unconnected-(H4-MOUNT-PadB3,0)") (class "Default")
      (node (ref "H4") (pin "B3,0") (pinfunction "MOUNT_B3,0") (pintype "passive"))
    )
    (net (code "83") (name "unconnected-(IC1-PB6(XTAL1{slash}TOSC1)-Pad9)") (class "Default")
      (node (ref "IC1") (pin "9") (pinfunction "PB6(XTAL1/TOSC1)_9") (pintype "bidirectional"))
    )
    (net (code "84") (name "unconnected-(IC1-PB7(XTAL2{slash}TOSC2)-Pad10)") (class "Default")
      (node (ref "IC1") (pin "10") (pinfunction "PB7(XTAL2/TOSC2)_10") (pintype "bidirectional"))
    )
    (net (code "85") (name "unconnected-(IC1-PC0(ADC0)-Pad23)") (class "Default")
      (node (ref "IC1") (pin "23") (pinfunction "PC0(ADC0)_23") (pintype "bidirectional"))
    )
    (net (code "86") (name "unconnected-(IC1-PC1(ADC1)-Pad24)") (class "Default")
      (node (ref "IC1") (pin "24") (pinfunction "PC1(ADC1)_24") (pintype "bidirectional"))
    )
    (net (code "87") (name "unconnected-(IC1-PC2(ADC2)-Pad25)") (class "Default")
      (node (ref "IC1") (pin "25") (pinfunction "PC2(ADC2)_25") (pintype "bidirectional"))
    )
    (net (code "88") (name "unconnected-(IC1-PC3(ADC3)-Pad26)") (class "Default")
      (node (ref "IC1") (pin "26") (pinfunction "PC3(ADC3)_26") (pintype "bidirectional"))
    )
    (net (code "89") (name "unconnected-(IC1-PC4(ADC4{slash}SDA)-Pad27)") (class "Default")
      (node (ref "IC1") (pin "27") (pinfunction "PC4(ADC4/SDA)_27") (pintype "bidirectional"))
    )
    (net (code "90") (name "unconnected-(IC3-PB6(XTAL1{slash}TOSC1)-Pad9)") (class "Default")
      (node (ref "IC3") (pin "9") (pinfunction "PB6(XTAL1/TOSC1)_9") (pintype "bidirectional"))
    )
    (net (code "91") (name "unconnected-(IC3-PB7(XTAL2{slash}TOSC2)-Pad10)") (class "Default")
      (node (ref "IC3") (pin "10") (pinfunction "PB7(XTAL2/TOSC2)_10") (pintype "bidirectional"))
    )
    (net (code "92") (name "unconnected-(IC3-PC0(ADC0)-Pad23)") (class "Default")
      (node (ref "IC3") (pin "23") (pinfunction "PC0(ADC0)_23") (pintype "bidirectional"))
    )
    (net (code "93") (name "unconnected-(IC3-PC1(ADC1)-Pad24)") (class "Default")
      (node (ref "IC3") (pin "24") (pinfunction "PC1(ADC1)_24") (pintype "bidirectional"))
    )
    (net (code "94") (name "unconnected-(IC3-PC2(ADC2)-Pad25)") (class "Default")
      (node (ref "IC3") (pin "25") (pinfunction "PC2(ADC2)_25") (pintype "bidirectional"))
    )
    (net (code "95") (name "unconnected-(OK2D-A-Pad7)") (class "Default")
      (node (ref "OK2") (pin "7") (pinfunction "A_7") (pintype "passive"))
    )
    (net (code "96") (name "unconnected-(OK2D-C-Pad8)") (class "Default")
      (node (ref "OK2") (pin "8") (pinfunction "C_8") (pintype "passive"))
    )
    (net (code "97") (name "unconnected-(OK2D-COL-Pad10)") (class "Default")
      (node (ref "OK2") (pin "10") (pinfunction "COL_10") (pintype "passive"))
    )
    (net (code "98") (name "unconnected-(OK2D-EMIT-Pad9)") (class "Default")
      (node (ref "OK2") (pin "9") (pinfunction "EMIT_9") (pintype "passive"))
    )
    (net (code "99") (name "unconnected-(SV2-Pad2)") (class "Default")
      (node (ref "SV2") (pin "2") (pinfunction "2_2") (pintype "passive"))
    )
    (net (code "100") (name "unconnected-(SV2-Pad8)") (class "Default")
      (node (ref "SV2") (pin "8") (pinfunction "8_8") (pintype "passive"))
    )
    (net (code "101") (name "unconnected-(SV2-Pad12)") (class "Default")
      (node (ref "SV2") (pin "12") (pinfunction "12_12") (pintype "passive"))
    )
    (net (code "102") (name "unconnected-(SV2-Pad13)") (class "Default")
      (node (ref "SV2") (pin "13") (pinfunction "13_13") (pintype "passive"))
    )
    (net (code "103") (name "unconnected-(SV2-Pad14)") (class "Default")
      (node (ref "SV2") (pin "14") (pinfunction "14_14") (pintype "passive"))
    )
    (net (code "104") (name "unconnected-(SV2-Pad15)") (class "Default")
      (node (ref "SV2") (pin "15") (pinfunction "15_15") (pintype "passive"))
    )
    (net (code "105") (name "unconnected-(SV2-Pad16)") (class "Default")
      (node (ref "SV2") (pin "16") (pinfunction "16_16") (pintype "passive"))
    )
    (net (code "106") (name "unconnected-(U2-CBUS2-Pad13)") (class "Default")
      (node (ref "U2") (pin "13") (pinfunction "CBUS2_13") (pintype "bidirectional"))
    )
    (net (code "107") (name "unconnected-(U2-CBUS3-Pad14)") (class "Default")
      (node (ref "U2") (pin "14") (pinfunction "CBUS3_14") (pintype "bidirectional"))
    )
    (net (code "108") (name "unconnected-(U2-CBUS4-Pad12)") (class "Default")
      (node (ref "U2") (pin "12") (pinfunction "CBUS4_12") (pintype "bidirectional"))
    )
    (net (code "109") (name "unconnected-(U2-CTS#-Pad11)") (class "Default")
      (node (ref "U2") (pin "11") (pinfunction "CTS#_11") (pintype "input"))
    )
    (net (code "110") (name "unconnected-(U2-DCD#-Pad10)") (class "Default")
      (node (ref "U2") (pin "10") (pinfunction "DCD#_10") (pintype "input"))
    )
    (net (code "111") (name "unconnected-(U2-DSR#-Pad9)") (class "Default")
      (node (ref "U2") (pin "9") (pinfunction "DSR#_9") (pintype "input"))
    )
    (net (code "112") (name "unconnected-(U2-DTR#-Pad2)") (class "Default")
      (node (ref "U2") (pin "2") (pinfunction "DTR#_2") (pintype "output"))
    )
    (net (code "113") (name "unconnected-(U2-OSCI-Pad27)") (class "Default")
      (node (ref "U2") (pin "27") (pinfunction "OSCI_27") (pintype "input"))
    )
    (net (code "114") (name "unconnected-(U2-OSCO-Pad28)") (class "Default")
      (node (ref "U2") (pin "28") (pinfunction "OSCO_28") (pintype "output"))
    )
    (net (code "115") (name "unconnected-(U2-RI#-Pad6)") (class "Default")
      (node (ref "U2") (pin "6") (pinfunction "RI#_6") (pintype "input"))
    )
    (net (code "116") (name "unconnected-(U2-RTS#-Pad3)") (class "Default")
      (node (ref "U2") (pin "3") (pinfunction "RTS#_3") (pintype "output"))
    )
    (net (code "117") (name "unconnected-(USB-Pad1)") (class "Default")
      (node (ref "USB") (pin "1") (pinfunction "1_1") (pintype "passive"))
    )
  )
)
